# power_board.net
KiCad netlist of a schematic drawn in EAGLE
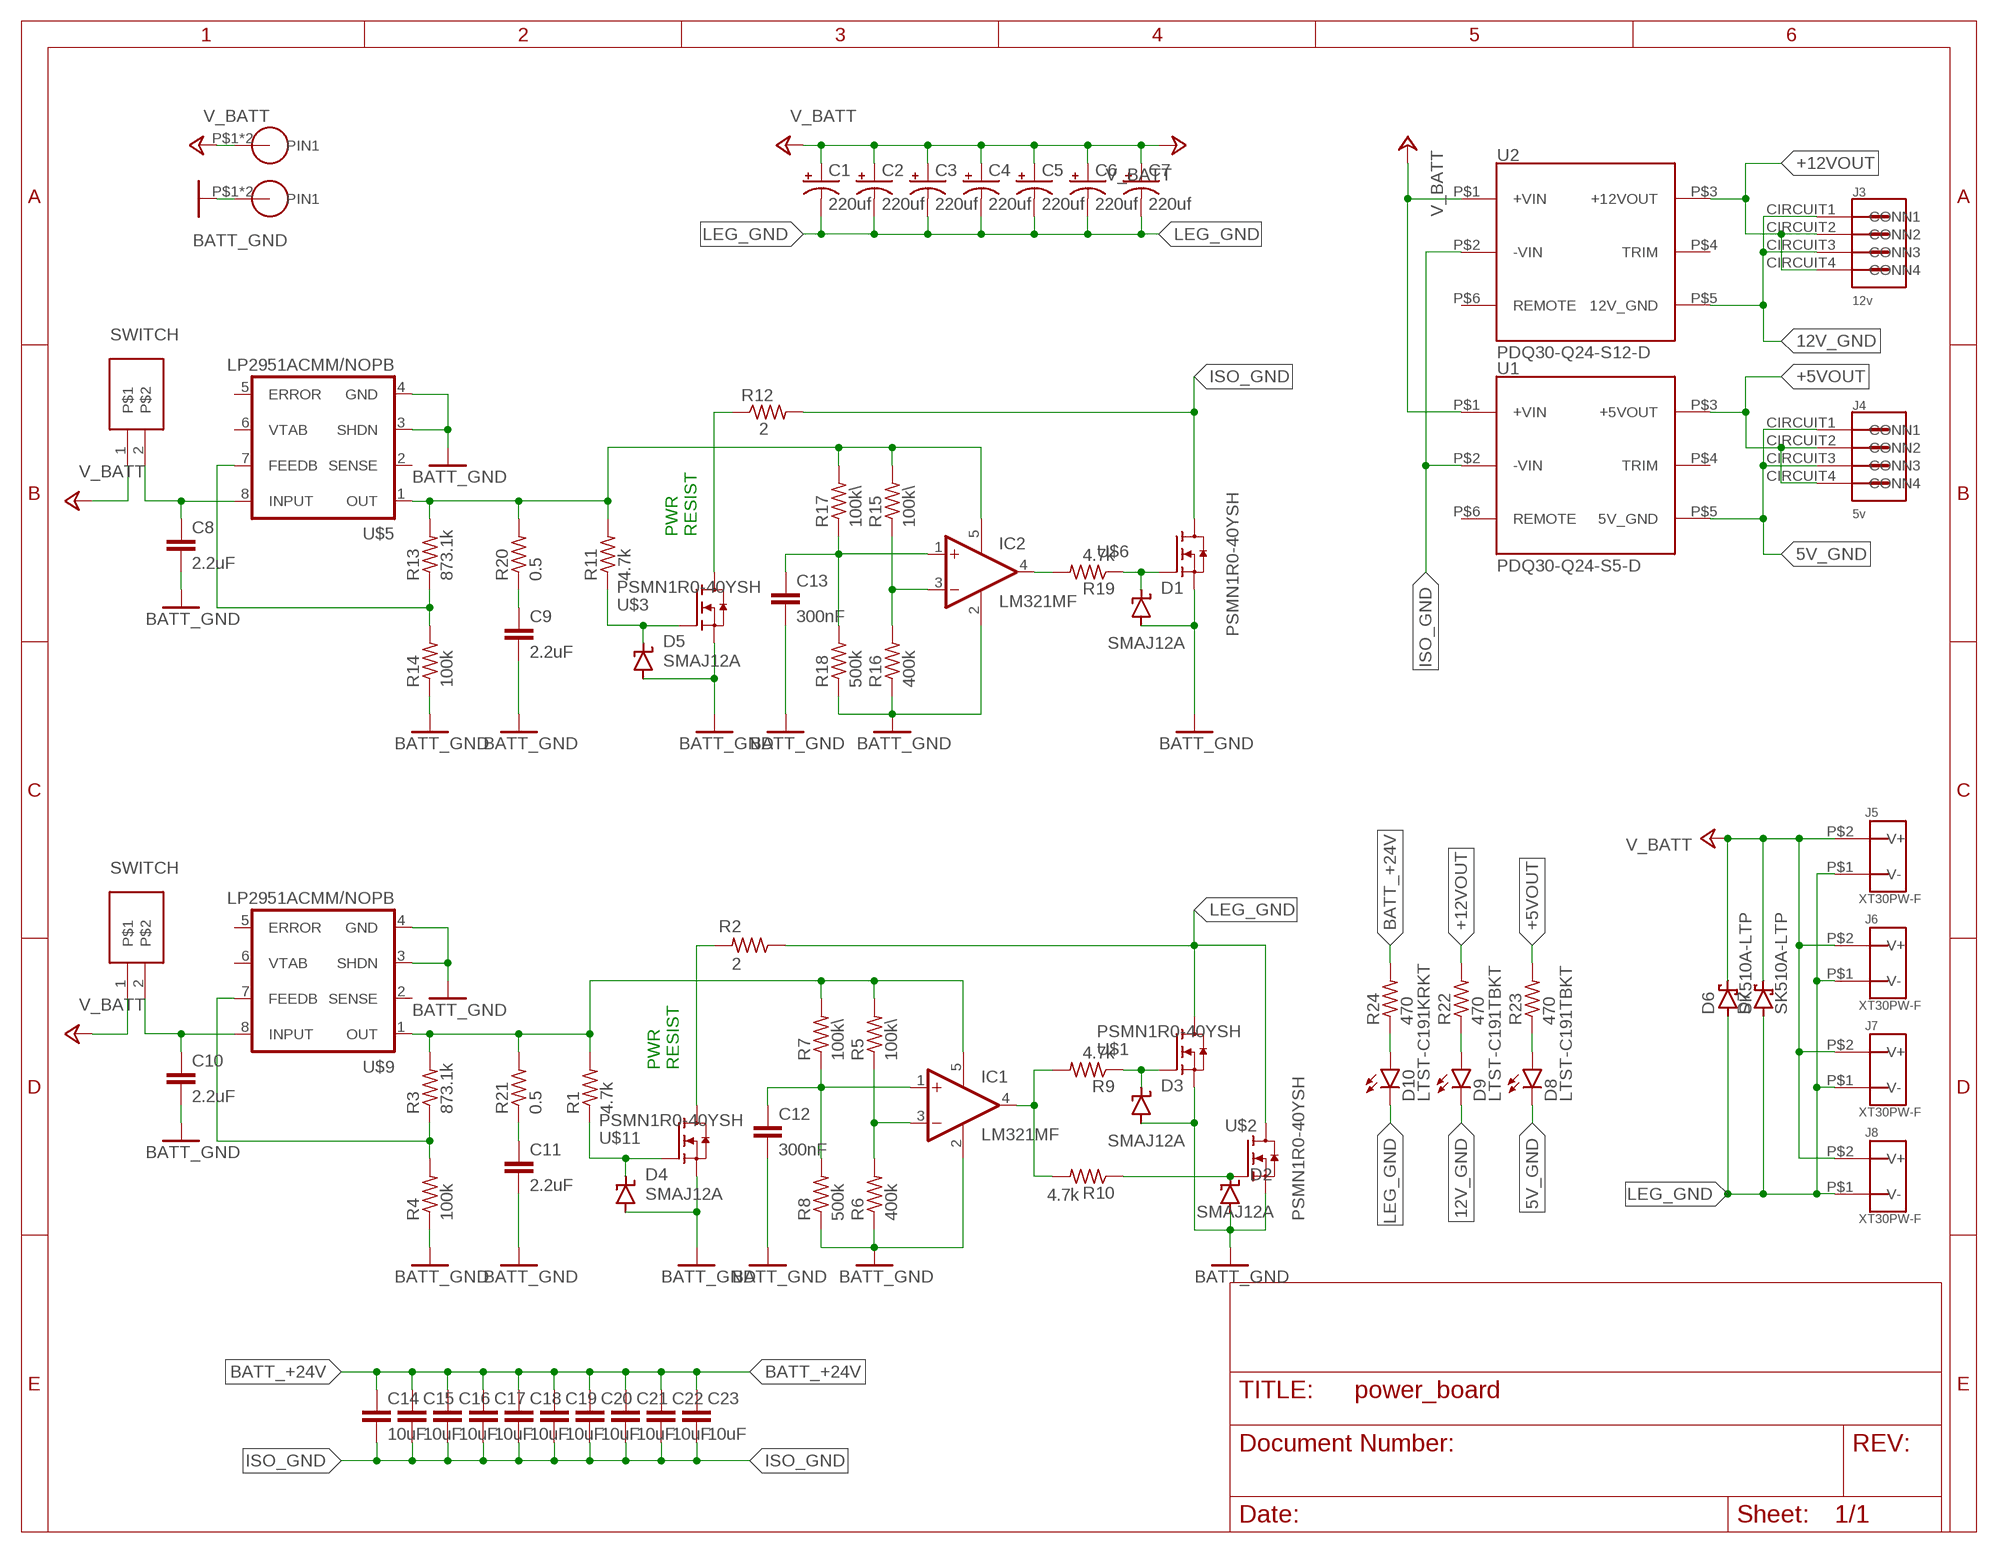
[diagram p0: schematic, sheet 1]

(export (version "E")
  (design (tool "Eeschema 10.0.6"))
  (components
    (comp (ref "C1")
      (value "220uf")
      (footprint "eagle-import:C_ELEC_8X11_5")
      (libsource (lib "eagle-import") (part "35ZLH220MEFC8X11.5"))
    )
    (comp (ref "C2")
      (value "220uf")
      (footprint "eagle-import:C_ELEC_8X11_5")
      (libsource (lib "eagle-import") (part "35ZLH220MEFC8X11.5"))
    )
    (comp (ref "C3")
      (value "220uf")
      (footprint "eagle-import:C_ELEC_8X11_5")
      (libsource (lib "eagle-import") (part "35ZLH220MEFC8X11.5"))
    )
    (comp (ref "C4")
      (value "220uf")
      (footprint "eagle-import:C_ELEC_8X11_5")
      (libsource (lib "eagle-import") (part "35ZLH220MEFC8X11.5"))
    )
    (comp (ref "C5")
      (value "220uf")
      (footprint "eagle-import:C_ELEC_8X11_5")
      (libsource (lib "eagle-import") (part "35ZLH220MEFC8X11.5"))
    )
    (comp (ref "C6")
      (value "220uf")
      (footprint "eagle-import:C_ELEC_8X11_5")
      (libsource (lib "eagle-import") (part "35ZLH220MEFC8X11.5"))
    )
    (comp (ref "C7")
      (value "220uf")
      (footprint "eagle-import:C_ELEC_8X11_5")
      (libsource (lib "eagle-import") (part "35ZLH220MEFC8X11.5"))
    )
    (comp (ref "C8")
      (value "2.2uF")
      (footprint "eagle-import:C0603")
      (libsource (lib "eagle-import") (part "C_CERAMIC_0603"))
    )
    (comp (ref "C9")
      (value "2.2uF")
      (footprint "eagle-import:C0603")
      (libsource (lib "eagle-import") (part "C_CERAMIC_0603"))
    )
    (comp (ref "C10")
      (value "2.2uF")
      (footprint "eagle-import:C0603")
      (libsource (lib "eagle-import") (part "C_CERAMIC_0603"))
    )
    (comp (ref "C11")
      (value "2.2uF")
      (footprint "eagle-import:C0603")
      (libsource (lib "eagle-import") (part "C_CERAMIC_0603"))
    )
    (comp (ref "C12")
      (value "300nF")
      (footprint "eagle-import:C0603")
      (libsource (lib "eagle-import") (part "C_CERAMIC_0603"))
    )
    (comp (ref "C13")
      (value "300nF")
      (footprint "eagle-import:C0603")
      (libsource (lib "eagle-import") (part "C_CERAMIC_0603"))
    )
    (comp (ref "C14")
      (value "10uF")
      (footprint "eagle-import:C1210")
      (libsource (lib "eagle-import") (part "C_CERAMIC_1210"))
    )
    (comp (ref "C15")
      (value "10uF")
      (footprint "eagle-import:C1210")
      (libsource (lib "eagle-import") (part "C_CERAMIC_1210"))
    )
    (comp (ref "C16")
      (value "10uF")
      (footprint "eagle-import:C1210")
      (libsource (lib "eagle-import") (part "C_CERAMIC_1210"))
    )
    (comp (ref "C17")
      (value "10uF")
      (footprint "eagle-import:C1210")
      (libsource (lib "eagle-import") (part "C_CERAMIC_1210"))
    )
    (comp (ref "C18")
      (value "10uF")
      (footprint "eagle-import:C1210")
      (libsource (lib "eagle-import") (part "C_CERAMIC_1210"))
    )
    (comp (ref "C19")
      (value "10uF")
      (footprint "eagle-import:C1210")
      (libsource (lib "eagle-import") (part "C_CERAMIC_1210"))
    )
    (comp (ref "C20")
      (value "10uF")
      (footprint "eagle-import:C1210")
      (libsource (lib "eagle-import") (part "C_CERAMIC_1210"))
    )
    (comp (ref "C21")
      (value "10uF")
      (footprint "eagle-import:C1210")
      (libsource (lib "eagle-import") (part "C_CERAMIC_1210"))
    )
    (comp (ref "C22")
      (value "10uF")
      (footprint "eagle-import:C1210")
      (libsource (lib "eagle-import") (part "C_CERAMIC_1210"))
    )
    (comp (ref "C23")
      (value "10uF")
      (footprint "eagle-import:C1210")
      (libsource (lib "eagle-import") (part "C_CERAMIC_1210"))
    )
    (comp (ref "D1")
      (value "SMAJ12A")
      (footprint "eagle-import:DO-214AC")
      (libsource (lib "eagle-import") (part "SMAJ12A"))
    )
    (comp (ref "D2")
      (value "SMAJ12A")
      (footprint "eagle-import:DO-214AC")
      (libsource (lib "eagle-import") (part "SMAJ12A"))
    )
    (comp (ref "D3")
      (value "SMAJ12A")
      (footprint "eagle-import:DO-214AC")
      (libsource (lib "eagle-import") (part "SMAJ12A"))
    )
    (comp (ref "D4")
      (value "SMAJ12A")
      (footprint "eagle-import:DO-214AC")
      (libsource (lib "eagle-import") (part "SMAJ12A"))
    )
    (comp (ref "D5")
      (value "SMAJ12A")
      (footprint "eagle-import:DO-214AC")
      (libsource (lib "eagle-import") (part "SMAJ12A"))
    )
    (comp (ref "D6")
      (value "SK510A-LTP")
      (footprint "eagle-import:DO-214AC")
      (libsource (lib "eagle-import") (part "SK510A-LTP"))
    )
    (comp (ref "D7")
      (value "SK510A-LTP")
      (footprint "eagle-import:DO-214AC")
      (libsource (lib "eagle-import") (part "SK510A-LTP"))
    )
    (comp (ref "D8")
      (value "LTST-C191TBKT")
      (footprint "eagle-import:LTST-C191TBKT")
      (libsource (lib "eagle-import") (part "LTST-C19?1TBKT"))
    )
    (comp (ref "D9")
      (value "LTST-C191TBKT")
      (footprint "eagle-import:LTST-C191TBKT")
      (libsource (lib "eagle-import") (part "LTST-C19?1TBKT"))
    )
    (comp (ref "D10")
      (value "LTST-C191KRKT")
      (footprint "eagle-import:LTST-C191TBKT")
      (libsource (lib "eagle-import") (part "LTST-C19?1KRKT"))
    )
    (comp (ref "IC1")
      (value "LM321MF")
      (footprint "eagle-import:SOT23-5")
      (libsource (lib "eagle-import") (part "LM321?MF"))
    )
    (comp (ref "IC2")
      (value "LM321MF")
      (footprint "eagle-import:SOT23-5")
      (libsource (lib "eagle-import") (part "LM321?MF"))
    )
    (comp (ref "J1")
      (value "FASTON1289_ST")
      (footprint "eagle-import:FASTON_1289-ST")
      (libsource (lib "eagle-import") (part "FASTON1289_ST"))
    )
    (comp (ref "J2")
      (value "FASTON1289_ST")
      (footprint "eagle-import:FASTON_1289-ST")
      (libsource (lib "eagle-import") (part "FASTON1289_ST"))
    )
    (comp (ref "J3")
      (value "12v")
      (footprint "eagle-import:MOLEX_4_RA")
      (libsource (lib "eagle-import") (part "MOLEX_4_RA"))
    )
    (comp (ref "J4")
      (value "5v")
      (footprint "eagle-import:MOLEX_4_RA")
      (libsource (lib "eagle-import") (part "MOLEX_4_RA"))
    )
    (comp (ref "J5")
      (value "XT30PW-F")
      (footprint "eagle-import:XT30PW-F")
      (libsource (lib "eagle-import") (part "XT30PW-F"))
    )
    (comp (ref "J6")
      (value "XT30PW-F")
      (footprint "eagle-import:XT30PW-F")
      (libsource (lib "eagle-import") (part "XT30PW-F"))
    )
    (comp (ref "J7")
      (value "XT30PW-F")
      (footprint "eagle-import:XT30PW-F")
      (libsource (lib "eagle-import") (part "XT30PW-F"))
    )
    (comp (ref "J8")
      (value "XT30PW-F")
      (footprint "eagle-import:XT30PW-F")
      (libsource (lib "eagle-import") (part "XT30PW-F"))
    )
    (comp (ref "R1")
      (value "4.7k")
      (footprint "eagle-import:R0603")
      (libsource (lib "eagle-import") (part "R-US_R0603"))
    )
    (comp (ref "R2")
      (value "2")
      (footprint "eagle-import:PWR163")
      (libsource (lib "eagle-import") (part "PWR163"))
    )
    (comp (ref "R3")
      (value "873.1k")
      (footprint "eagle-import:R0603")
      (libsource (lib "eagle-import") (part "R-US_R0603"))
    )
    (comp (ref "R4")
      (value "100k")
      (footprint "eagle-import:R0603")
      (libsource (lib "eagle-import") (part "R-US_R0603"))
    )
    (comp (ref "R5")
      (value "100k\\")
      (footprint "eagle-import:R0603")
      (libsource (lib "eagle-import") (part "R-US_R0603"))
    )
    (comp (ref "R6")
      (value "400k")
      (footprint "eagle-import:R0603")
      (libsource (lib "eagle-import") (part "R-US_R0603"))
    )
    (comp (ref "R7")
      (value "100k\\")
      (footprint "eagle-import:R0603")
      (libsource (lib "eagle-import") (part "R-US_R0603"))
    )
    (comp (ref "R8")
      (value "500k")
      (footprint "eagle-import:R0603")
      (libsource (lib "eagle-import") (part "R-US_R0603"))
    )
    (comp (ref "R9")
      (value "4.7k")
      (footprint "eagle-import:R0603")
      (libsource (lib "eagle-import") (part "R-US_R0603"))
    )
    (comp (ref "R10")
      (value "4.7k")
      (footprint "eagle-import:R0603")
      (libsource (lib "eagle-import") (part "R-US_R0603"))
    )
    (comp (ref "R11")
      (value "4.7k")
      (footprint "eagle-import:R0603")
      (libsource (lib "eagle-import") (part "R-US_R0603"))
    )
    (comp (ref "R12")
      (value "2")
      (footprint "eagle-import:PWR163")
      (libsource (lib "eagle-import") (part "PWR163"))
    )
    (comp (ref "R13")
      (value "873.1k")
      (footprint "eagle-import:R0603")
      (libsource (lib "eagle-import") (part "R-US_R0603"))
    )
    (comp (ref "R14")
      (value "100k")
      (footprint "eagle-import:R0603")
      (libsource (lib "eagle-import") (part "R-US_R0603"))
    )
    (comp (ref "R15")
      (value "100k\\")
      (footprint "eagle-import:R0603")
      (libsource (lib "eagle-import") (part "R-US_R0603"))
    )
    (comp (ref "R16")
      (value "400k")
      (footprint "eagle-import:R0603")
      (libsource (lib "eagle-import") (part "R-US_R0603"))
    )
    (comp (ref "R17")
      (value "100k\\")
      (footprint "eagle-import:R0603")
      (libsource (lib "eagle-import") (part "R-US_R0603"))
    )
    (comp (ref "R18")
      (value "500k")
      (footprint "eagle-import:R0603")
      (libsource (lib "eagle-import") (part "R-US_R0603"))
    )
    (comp (ref "R19")
      (value "4.7k")
      (footprint "eagle-import:R0603")
      (libsource (lib "eagle-import") (part "R-US_R0603"))
    )
    (comp (ref "R20")
      (value "0.5")
      (footprint "eagle-import:R0603")
      (libsource (lib "eagle-import") (part "R-US_R0603"))
    )
    (comp (ref "R21")
      (value "0.5")
      (footprint "eagle-import:R0603")
      (libsource (lib "eagle-import") (part "R-US_R0603"))
    )
    (comp (ref "R22")
      (value "470")
      (footprint "eagle-import:R0603")
      (libsource (lib "eagle-import") (part "R-US_R0603"))
    )
    (comp (ref "R23")
      (value "470")
      (footprint "eagle-import:R0603")
      (libsource (lib "eagle-import") (part "R-US_R0603"))
    )
    (comp (ref "R24")
      (value "470")
      (footprint "eagle-import:R0603")
      (libsource (lib "eagle-import") (part "R-US_R0603"))
    )
    (comp (ref "U$1")
      (value "PSMN1R0-40YSH")
      (footprint "eagle-import:LFPAK56E")
      (libsource (lib "eagle-import") (part "PSMN1R0-40YSH"))
    )
    (comp (ref "U$2")
      (value "PSMN1R0-40YSH")
      (footprint "eagle-import:LFPAK56E")
      (libsource (lib "eagle-import") (part "PSMN1R0-40YSH"))
    )
    (comp (ref "U$3")
      (value "PSMN1R0-40YSH")
      (footprint "eagle-import:LFPAK56E")
      (libsource (lib "eagle-import") (part "PSMN1R0-40YSH"))
    )
    (comp (ref "U$5")
      (value "LP2951ACMM/NOPB")
      (footprint "eagle-import:LP2591")
      (libsource (lib "eagle-import") (part "LP2951ACMM/NOPB"))
    )
    (comp (ref "U$6")
      (value "PSMN1R0-40YSH")
      (footprint "eagle-import:LFPAK56E")
      (libsource (lib "eagle-import") (part "PSMN1R0-40YSH"))
    )
    (comp (ref "U$9")
      (value "LP2951ACMM/NOPB")
      (footprint "eagle-import:LP2591")
      (libsource (lib "eagle-import") (part "LP2951ACMM/NOPB"))
    )
    (comp (ref "U$11")
      (value "PSMN1R0-40YSH")
      (footprint "eagle-import:LFPAK56E")
      (libsource (lib "eagle-import") (part "PSMN1R0-40YSH"))
    )
    (comp (ref "U$26")
      (value "2-PIN")
      (footprint "eagle-import:M80-8420242")
      (libsource (lib "eagle-import") (part "2-PIN"))
    )
    (comp (ref "U$27")
      (value "2-PIN")
      (footprint "eagle-import:M80-8420242")
      (libsource (lib "eagle-import") (part "2-PIN"))
    )
    (comp (ref "U1")
      (value "PDQ30-Q24-S5-D")
      (footprint "eagle-import:PDQ30-D")
      (libsource (lib "eagle-import") (part "PDQ30-Q24-S5-D"))
    )
    (comp (ref "U2")
      (value "PDQ30-Q24-S12-D")
      (footprint "eagle-import:PDQ30-D")
      (libsource (lib "eagle-import") (part "PDQ30-Q24-S12-D"))
    )
  )
  (nets
    (net (code "1") (name "+5VOUT") (class "Default")
      (node (ref "J4") (pin "CIRCUIT2") (pinfunction "CONN2_CIRCUIT2") (pintype "power_in"))
      (node (ref "J4") (pin "CIRCUIT4") (pinfunction "CONN4_CIRCUIT4") (pintype "power_in"))
      (node (ref "R23") (pin "2") (pinfunction "2_2") (pintype "passive"))
      (node (ref "U1") (pin "P$3") (pinfunction "+5VOUT_P$3") (pintype "power_in"))
    )
    (net (code "2") (name "+12VOUT") (class "Default")
      (node (ref "J3") (pin "CIRCUIT2") (pinfunction "CONN2_CIRCUIT2") (pintype "power_in"))
      (node (ref "J3") (pin "CIRCUIT4") (pinfunction "CONN4_CIRCUIT4") (pintype "power_in"))
      (node (ref "R22") (pin "2") (pinfunction "2_2") (pintype "passive"))
      (node (ref "U2") (pin "P$3") (pinfunction "+12VOUT_P$3") (pintype "power_in"))
    )
    (net (code "3") (name "5V_GND") (class "Default")
      (node (ref "D8") (pin "C") (pinfunction "C_C") (pintype "passive"))
      (node (ref "J4") (pin "CIRCUIT1") (pinfunction "CONN1_CIRCUIT1") (pintype "power_in"))
      (node (ref "J4") (pin "CIRCUIT3") (pinfunction "CONN3_CIRCUIT3") (pintype "power_in"))
      (node (ref "U1") (pin "P$5") (pinfunction "5V_GND_P$5") (pintype "power_in"))
    )
    (net (code "4") (name "12V_GND") (class "Default")
      (node (ref "D9") (pin "C") (pinfunction "C_C") (pintype "passive"))
      (node (ref "J3") (pin "CIRCUIT1") (pinfunction "CONN1_CIRCUIT1") (pintype "power_in"))
      (node (ref "J3") (pin "CIRCUIT3") (pinfunction "CONN3_CIRCUIT3") (pintype "power_in"))
      (node (ref "U2") (pin "P$5") (pinfunction "12V_GND_P$5") (pintype "power_in"))
    )
    (net (code "5") (name "BATT_+24V") (class "Default")
      (node (ref "C1") (pin "1") (pinfunction "+_1") (pintype "passive"))
      (node (ref "C14") (pin "1") (pinfunction "1_1") (pintype "passive"))
      (node (ref "C15") (pin "1") (pinfunction "1_1") (pintype "passive"))
      (node (ref "C16") (pin "1") (pinfunction "1_1") (pintype "passive"))
      (node (ref "C17") (pin "1") (pinfunction "1_1") (pintype "passive"))
      (node (ref "C18") (pin "1") (pinfunction "1_1") (pintype "passive"))
      (node (ref "C19") (pin "1") (pinfunction "1_1") (pintype "passive"))
      (node (ref "C2") (pin "1") (pinfunction "+_1") (pintype "passive"))
      (node (ref "C20") (pin "1") (pinfunction "1_1") (pintype "passive"))
      (node (ref "C21") (pin "1") (pinfunction "1_1") (pintype "passive"))
      (node (ref "C22") (pin "1") (pinfunction "1_1") (pintype "passive"))
      (node (ref "C23") (pin "1") (pinfunction "1_1") (pintype "passive"))
      (node (ref "C3") (pin "1") (pinfunction "+_1") (pintype "passive"))
      (node (ref "C4") (pin "1") (pinfunction "+_1") (pintype "passive"))
      (node (ref "C5") (pin "1") (pinfunction "+_1") (pintype "passive"))
      (node (ref "C6") (pin "1") (pinfunction "+_1") (pintype "passive"))
      (node (ref "C7") (pin "1") (pinfunction "+_1") (pintype "passive"))
      (node (ref "D6") (pin "C") (pinfunction "C_C") (pintype "passive"))
      (node (ref "D7") (pin "C") (pinfunction "C_C") (pintype "passive"))
      (node (ref "J1") (pin "P$1") (pinfunction "PIN1_P$1") (pintype "bidirectional"))
      (node (ref "J1") (pin "P$2") (pinfunction "PIN1_P$2") (pintype "bidirectional"))
      (node (ref "J5") (pin "P$2") (pinfunction "V+_P$2") (pintype "bidirectional"))
      (node (ref "J6") (pin "P$2") (pinfunction "V+_P$2") (pintype "bidirectional"))
      (node (ref "J7") (pin "P$2") (pinfunction "V+_P$2") (pintype "bidirectional"))
      (node (ref "J8") (pin "P$2") (pinfunction "V+_P$2") (pintype "bidirectional"))
      (node (ref "R24") (pin "2") (pinfunction "2_2") (pintype "passive"))
      (node (ref "U$26") (pin "1") (pinfunction "P$1_1") (pintype "bidirectional"))
      (node (ref "U$27") (pin "1") (pinfunction "P$1_1") (pintype "bidirectional"))
      (node (ref "U1") (pin "P$1") (pinfunction "+VIN_P$1") (pintype "power_in"))
      (node (ref "U2") (pin "P$1") (pinfunction "+VIN_P$1") (pintype "power_in"))
    )
    (net (code "6") (name "BATT_GND") (class "Default")
      (node (ref "C10") (pin "2") (pinfunction "2_2") (pintype "passive"))
      (node (ref "C11") (pin "2") (pinfunction "2_2") (pintype "passive"))
      (node (ref "C12") (pin "2") (pinfunction "2_2") (pintype "passive"))
      (node (ref "C13") (pin "2") (pinfunction "2_2") (pintype "passive"))
      (node (ref "C8") (pin "2") (pinfunction "2_2") (pintype "passive"))
      (node (ref "C9") (pin "2") (pinfunction "2_2") (pintype "passive"))
      (node (ref "D1") (pin "A") (pinfunction "A_A") (pintype "passive"))
      (node (ref "D2") (pin "A") (pinfunction "A_A") (pintype "passive"))
      (node (ref "D3") (pin "A") (pinfunction "A_A") (pintype "passive"))
      (node (ref "D4") (pin "A") (pinfunction "A_A") (pintype "passive"))
      (node (ref "D5") (pin "A") (pinfunction "A_A") (pintype "passive"))
      (node (ref "IC1") (pin "2") (pinfunction "V-_2") (pintype "power_in"))
      (node (ref "IC2") (pin "2") (pinfunction "V-_2") (pintype "power_in"))
      (node (ref "J2") (pin "P$1") (pinfunction "PIN1_P$1") (pintype "bidirectional"))
      (node (ref "J2") (pin "P$2") (pinfunction "PIN1_P$2") (pintype "bidirectional"))
      (node (ref "R14") (pin "1") (pinfunction "1_1") (pintype "passive"))
      (node (ref "R16") (pin "1") (pinfunction "1_1") (pintype "passive"))
      (node (ref "R18") (pin "1") (pinfunction "1_1") (pintype "passive"))
      (node (ref "R4") (pin "1") (pinfunction "1_1") (pintype "passive"))
      (node (ref "R6") (pin "1") (pinfunction "1_1") (pintype "passive"))
      (node (ref "R8") (pin "1") (pinfunction "1_1") (pintype "passive"))
      (node (ref "U$1") (pin "1") (pinfunction "S_1") (pintype "passive"))
      (node (ref "U$1") (pin "2") (pinfunction "S_2") (pintype "passive"))
      (node (ref "U$1") (pin "3") (pinfunction "S_3") (pintype "passive"))
      (node (ref "U$11") (pin "1") (pinfunction "S_1") (pintype "passive"))
      (node (ref "U$11") (pin "2") (pinfunction "S_2") (pintype "passive"))
      (node (ref "U$11") (pin "3") (pinfunction "S_3") (pintype "passive"))
      (node (ref "U$2") (pin "1") (pinfunction "S_1") (pintype "passive"))
      (node (ref "U$2") (pin "2") (pinfunction "S_2") (pintype "passive"))
      (node (ref "U$2") (pin "3") (pinfunction "S_3") (pintype "passive"))
      (node (ref "U$3") (pin "1") (pinfunction "S_1") (pintype "passive"))
      (node (ref "U$3") (pin "2") (pinfunction "S_2") (pintype "passive"))
      (node (ref "U$3") (pin "3") (pinfunction "S_3") (pintype "passive"))
      (node (ref "U$5") (pin "3") (pinfunction "SHDN_3") (pintype "input"))
      (node (ref "U$5") (pin "4") (pinfunction "GND_4") (pintype "power_in"))
      (node (ref "U$6") (pin "1") (pinfunction "S_1") (pintype "passive"))
      (node (ref "U$6") (pin "2") (pinfunction "S_2") (pintype "passive"))
      (node (ref "U$6") (pin "3") (pinfunction "S_3") (pintype "passive"))
      (node (ref "U$9") (pin "3") (pinfunction "SHDN_3") (pintype "input"))
      (node (ref "U$9") (pin "4") (pinfunction "GND_4") (pintype "power_in"))
    )
    (net (code "7") (name "ISO_GND") (class "Default")
      (node (ref "C14") (pin "2") (pinfunction "2_2") (pintype "passive"))
      (node (ref "C15") (pin "2") (pinfunction "2_2") (pintype "passive"))
      (node (ref "C16") (pin "2") (pinfunction "2_2") (pintype "passive"))
      (node (ref "C17") (pin "2") (pinfunction "2_2") (pintype "passive"))
      (node (ref "C18") (pin "2") (pinfunction "2_2") (pintype "passive"))
      (node (ref "C19") (pin "2") (pinfunction "2_2") (pintype "passive"))
      (node (ref "C20") (pin "2") (pinfunction "2_2") (pintype "passive"))
      (node (ref "C21") (pin "2") (pinfunction "2_2") (pintype "passive"))
      (node (ref "C22") (pin "2") (pinfunction "2_2") (pintype "passive"))
      (node (ref "C23") (pin "2") (pinfunction "2_2") (pintype "passive"))
      (node (ref "R12") (pin "P$2") (pinfunction "2_P$2") (pintype "passive"))
      (node (ref "U$6") (pin "5") (pinfunction "D_5") (pintype "passive"))
      (node (ref "U1") (pin "P$2") (pinfunction "-VIN_P$2") (pintype "power_in"))
      (node (ref "U2") (pin "P$2") (pinfunction "-VIN_P$2") (pintype "power_in"))
    )
    (net (code "8") (name "LEG_GND") (class "Default")
      (node (ref "C1") (pin "2") (pinfunction "-_2") (pintype "passive"))
      (node (ref "C2") (pin "2") (pinfunction "-_2") (pintype "passive"))
      (node (ref "C3") (pin "2") (pinfunction "-_2") (pintype "passive"))
      (node (ref "C4") (pin "2") (pinfunction "-_2") (pintype "passive"))
      (node (ref "C5") (pin "2") (pinfunction "-_2") (pintype "passive"))
      (node (ref "C6") (pin "2") (pinfunction "-_2") (pintype "passive"))
      (node (ref "C7") (pin "2") (pinfunction "-_2") (pintype "passive"))
      (node (ref "D10") (pin "C") (pinfunction "C_C") (pintype "passive"))
      (node (ref "D6") (pin "A") (pinfunction "A_A") (pintype "passive"))
      (node (ref "D7") (pin "A") (pinfunction "A_A") (pintype "passive"))
      (node (ref "J5") (pin "P$1") (pinfunction "V-_P$1") (pintype "bidirectional"))
      (node (ref "J6") (pin "P$1") (pinfunction "V-_P$1") (pintype "bidirectional"))
      (node (ref "J7") (pin "P$1") (pinfunction "V-_P$1") (pintype "bidirectional"))
      (node (ref "J8") (pin "P$1") (pinfunction "V-_P$1") (pintype "bidirectional"))
      (node (ref "R2") (pin "P$1") (pinfunction "1_P$1") (pintype "passive"))
      (node (ref "U$1") (pin "5") (pinfunction "D_5") (pintype "passive"))
      (node (ref "U$2") (pin "5") (pinfunction "D_5") (pintype "passive"))
    )
    (net (code "9") (name "Net-(C9-Pad1)") (class "Default")
      (node (ref "C9") (pin "1") (pinfunction "1_1") (pintype "passive"))
      (node (ref "R20") (pin "1") (pinfunction "1_1") (pintype "passive"))
    )
    (net (code "10") (name "Net-(C11-Pad1)") (class "Default")
      (node (ref "C11") (pin "1") (pinfunction "1_1") (pintype "passive"))
      (node (ref "R21") (pin "1") (pinfunction "1_1") (pintype "passive"))
    )
    (net (code "11") (name "Net-(D8-PadA)") (class "Default")
      (node (ref "D8") (pin "A") (pinfunction "A_A") (pintype "passive"))
      (node (ref "R23") (pin "1") (pinfunction "1_1") (pintype "passive"))
    )
    (net (code "12") (name "Net-(D9-PadA)") (class "Default")
      (node (ref "D9") (pin "A") (pinfunction "A_A") (pintype "passive"))
      (node (ref "R22") (pin "1") (pinfunction "1_1") (pintype "passive"))
    )
    (net (code "13") (name "Net-(D10-PadA)") (class "Default")
      (node (ref "D10") (pin "A") (pinfunction "A_A") (pintype "passive"))
      (node (ref "R24") (pin "1") (pinfunction "1_1") (pintype "passive"))
    )
    (net (code "14") (name "Net-(IC1-+IN)") (class "Default")
      (node (ref "C12") (pin "1") (pinfunction "1_1") (pintype "passive"))
      (node (ref "IC1") (pin "1") (pinfunction "+IN_1") (pintype "input"))
      (node (ref "R7") (pin "1") (pinfunction "1_1") (pintype "passive"))
      (node (ref "R8") (pin "2") (pinfunction "2_2") (pintype "passive"))
    )
    (net (code "15") (name "Net-(IC1--IN)") (class "Default")
      (node (ref "IC1") (pin "3") (pinfunction "-IN_3") (pintype "input"))
      (node (ref "R5") (pin "1") (pinfunction "1_1") (pintype "passive"))
      (node (ref "R6") (pin "2") (pinfunction "2_2") (pintype "passive"))
    )
    (net (code "16") (name "Net-(IC1-OUT)") (class "Default")
      (node (ref "IC1") (pin "4") (pinfunction "OUT_4") (pintype "output"))
      (node (ref "R10") (pin "2") (pinfunction "2_2") (pintype "passive"))
      (node (ref "R9") (pin "2") (pinfunction "2_2") (pintype "passive"))
    )
    (net (code "17") (name "Net-(IC1-V+)") (class "Default")
      (node (ref "IC1") (pin "5") (pinfunction "V+_5") (pintype "power_in"))
      (node (ref "R1") (pin "2") (pinfunction "2_2") (pintype "passive"))
      (node (ref "R21") (pin "2") (pinfunction "2_2") (pintype "passive"))
      (node (ref "R3") (pin "2") (pinfunction "2_2") (pintype "passive"))
      (node (ref "R5") (pin "2") (pinfunction "2_2") (pintype "passive"))
      (node (ref "R7") (pin "2") (pinfunction "2_2") (pintype "passive"))
      (node (ref "U$9") (pin "1") (pinfunction "OUT_1") (pintype "output"))
    )
    (net (code "18") (name "Net-(IC2-+IN)") (class "Default")
      (node (ref "C13") (pin "1") (pinfunction "1_1") (pintype "passive"))
      (node (ref "IC2") (pin "1") (pinfunction "+IN_1") (pintype "input"))
      (node (ref "R17") (pin "1") (pinfunction "1_1") (pintype "passive"))
      (node (ref "R18") (pin "2") (pinfunction "2_2") (pintype "passive"))
    )
    (net (code "19") (name "Net-(IC2--IN)") (class "Default")
      (node (ref "IC2") (pin "3") (pinfunction "-IN_3") (pintype "input"))
      (node (ref "R15") (pin "1") (pinfunction "1_1") (pintype "passive"))
      (node (ref "R16") (pin "2") (pinfunction "2_2") (pintype "passive"))
    )
    (net (code "20") (name "Net-(IC2-OUT)") (class "Default")
      (node (ref "IC2") (pin "4") (pinfunction "OUT_4") (pintype "output"))
      (node (ref "R19") (pin "2") (pinfunction "2_2") (pintype "passive"))
    )
    (net (code "21") (name "Net-(IC2-V+)") (class "Default")
      (node (ref "IC2") (pin "5") (pinfunction "V+_5") (pintype "power_in"))
      (node (ref "R11") (pin "2") (pinfunction "2_2") (pintype "passive"))
      (node (ref "R13") (pin "2") (pinfunction "2_2") (pintype "passive"))
      (node (ref "R15") (pin "2") (pinfunction "2_2") (pintype "passive"))
      (node (ref "R17") (pin "2") (pinfunction "2_2") (pintype "passive"))
      (node (ref "R20") (pin "2") (pinfunction "2_2") (pintype "passive"))
      (node (ref "U$5") (pin "1") (pinfunction "OUT_1") (pintype "output"))
    )
    (net (code "22") (name "Net-(R2-2)") (class "Default")
      (node (ref "R2") (pin "P$2") (pinfunction "2_P$2") (pintype "passive"))
      (node (ref "U$11") (pin "5") (pinfunction "D_5") (pintype "passive"))
    )
    (net (code "23") (name "Net-(R12-1)") (class "Default")
      (node (ref "R12") (pin "P$1") (pinfunction "1_P$1") (pintype "passive"))
      (node (ref "U$3") (pin "5") (pinfunction "D_5") (pintype "passive"))
    )
    (net (code "24") (name "Net-(U$1-G)") (class "Default")
      (node (ref "D3") (pin "C") (pinfunction "C_C") (pintype "passive"))
      (node (ref "R9") (pin "1") (pinfunction "1_1") (pintype "passive"))
      (node (ref "U$1") (pin "4") (pinfunction "G_4") (pintype "passive"))
    )
    (net (code "25") (name "Net-(U$2-G)") (class "Default")
      (node (ref "D2") (pin "C") (pinfunction "C_C") (pintype "passive"))
      (node (ref "R10") (pin "1") (pinfunction "1_1") (pintype "passive"))
      (node (ref "U$2") (pin "4") (pinfunction "G_4") (pintype "passive"))
    )
    (net (code "26") (name "Net-(U$3-G)") (class "Default")
      (node (ref "D5") (pin "C") (pinfunction "C_C") (pintype "passive"))
      (node (ref "R11") (pin "1") (pinfunction "1_1") (pintype "passive"))
      (node (ref "U$3") (pin "4") (pinfunction "G_4") (pintype "passive"))
    )
    (net (code "27") (name "Net-(U$5-FEEDB)") (class "Default")
      (node (ref "R13") (pin "1") (pinfunction "1_1") (pintype "passive"))
      (node (ref "R14") (pin "2") (pinfunction "2_2") (pintype "passive"))
      (node (ref "U$5") (pin "7") (pinfunction "FEEDB_7") (pintype "output"))
    )
    (net (code "28") (name "Net-(U$6-G)") (class "Default")
      (node (ref "D1") (pin "C") (pinfunction "C_C") (pintype "passive"))
      (node (ref "R19") (pin "1") (pinfunction "1_1") (pintype "passive"))
      (node (ref "U$6") (pin "4") (pinfunction "G_4") (pintype "passive"))
    )
    (net (code "29") (name "Net-(U$9-FEEDB)") (class "Default")
      (node (ref "R3") (pin "1") (pinfunction "1_1") (pintype "passive"))
      (node (ref "R4") (pin "2") (pinfunction "2_2") (pintype "passive"))
      (node (ref "U$9") (pin "7") (pinfunction "FEEDB_7") (pintype "output"))
    )
    (net (code "30") (name "Net-(U$11-G)") (class "Default")
      (node (ref "D4") (pin "C") (pinfunction "C_C") (pintype "passive"))
      (node (ref "R1") (pin "1") (pinfunction "1_1") (pintype "passive"))
      (node (ref "U$11") (pin "4") (pinfunction "G_4") (pintype "passive"))
    )
    (net (code "31") (name "Net-(U$26-P$2)") (class "Default")
      (node (ref "C8") (pin "1") (pinfunction "1_1") (pintype "passive"))
      (node (ref "U$26") (pin "2") (pinfunction "P$2_2") (pintype "bidirectional"))
      (node (ref "U$5") (pin "8") (pinfunction "INPUT_8") (pintype "passive"))
    )
    (net (code "32") (name "Net-(U$27-P$2)") (class "Default")
      (node (ref "C10") (pin "1") (pinfunction "1_1") (pintype "passive"))
      (node (ref "U$27") (pin "2") (pinfunction "P$2_2") (pintype "bidirectional"))
      (node (ref "U$9") (pin "8") (pinfunction "INPUT_8") (pintype "passive"))
    )
    (net (code "33") (name "unconnected-(U$5-ERROR-Pad5)") (class "Default")
      (node (ref "U$5") (pin "5") (pinfunction "ERROR_5") (pintype "output"))
    )
    (net (code "34") (name "unconnected-(U$5-SENSE-Pad2)") (class "Default")
      (node (ref "U$5") (pin "2") (pinfunction "SENSE_2") (pintype "input"))
    )
    (net (code "35") (name "unconnected-(U$5-VTAB-Pad6)") (class "Default")
      (node (ref "U$5") (pin "6") (pinfunction "VTAB_6") (pintype "input"))
    )
    (net (code "36") (name "unconnected-(U$9-ERROR-Pad5)") (class "Default")
      (node (ref "U$9") (pin "5") (pinfunction "ERROR_5") (pintype "output"))
    )
    (net (code "37") (name "unconnected-(U$9-SENSE-Pad2)") (class "Default")
      (node (ref "U$9") (pin "2") (pinfunction "SENSE_2") (pintype "input"))
    )
    (net (code "38") (name "unconnected-(U$9-VTAB-Pad6)") (class "Default")
      (node (ref "U$9") (pin "6") (pinfunction "VTAB_6") (pintype "input"))
    )
    (net (code "39") (name "unconnected-(U1-REMOTE-PadP$6)") (class "Default")
      (node (ref "U1") (pin "P$6") (pinfunction "REMOTE_P$6") (pintype "bidirectional"))
    )
    (net (code "40") (name "unconnected-(U1-TRIM-PadP$4)") (class "Default")
      (node (ref "U1") (pin "P$4") (pinfunction "TRIM_P$4") (pintype "bidirectional"))
    )
    (net (code "41") (name "unconnected-(U2-REMOTE-PadP$6)") (class "Default")
      (node (ref "U2") (pin "P$6") (pinfunction "REMOTE_P$6") (pintype "bidirectional"))
    )
    (net (code "42") (name "unconnected-(U2-TRIM-PadP$4)") (class "Default")
      (node (ref "U2") (pin "P$4") (pinfunction "TRIM_P$4") (pintype "bidirectional"))
    )
  )
)
